# 400_FLAHS_MEMORY.net
KiCad netlist of a schematic drawn in Altium Designer
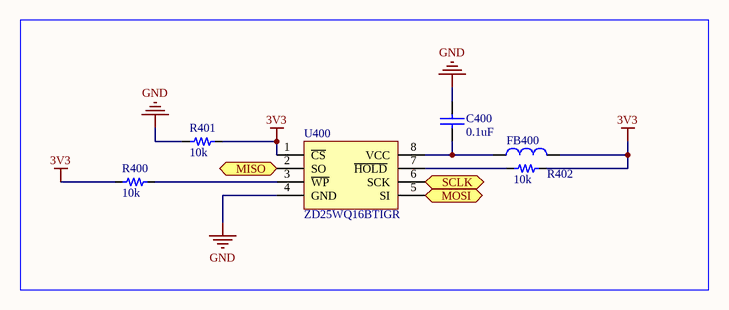
[diagram p0: 400_FLAHS_MEMORY.SchDoc]

(export (version "E")
  (design (tool "Eeschema 10.0.6"))
  (components
    (comp (ref "C400")
      (value "0.1uF")
      (footprint "0603_cap")
      (description "50V 100nF Y5V -20%~+80% 0603 Multilayer Ceramic Capacitors MLCC - SMD/SMT ROHS")
      (fields
        (field (name "MANUFACTURER") "Walsin Tech Corp")
        (field (name "MANUFACTURER PART NUMBER") "0603F104Z500CT")
      )
      (libsource (lib "shared_lib") (part "Cap_0.1uF_0603_50V"))
    )
    (comp (ref "FB400")
      (value "60OHM 2A")
      (footprint "0603_fb")
      (description "2A 1 100mΩ 60Ω@100MHz ±25% 0603 Ferrite Beads ROHS")
      (fields
        (field (name "MANUFACTURER") "TAI-TECH")
        (field (name "MANUFACTURER PART NUMBER") "HCB1608KF-600T20")
      )
      (libsource (lib "shared_lib") (part "FB_60_0603_2A"))
    )
    (comp (ref "R400")
      (value "10k")
      (footprint "0603_res")
      (description "RES SMD 10k OHM 5% 1/10W 0603")
      (fields (field (name "MANUFACTURER") "FOJAN") (field (name "MANUFACTURER PART NUMBER") "FRC0603J103TS"))
      (libsource (lib "shared_lib") (part "Res_10k_0603_1/10W"))
    )
    (comp (ref "R401")
      (value "10k")
      (footprint "0603_res")
      (description "RES SMD 10k OHM 5% 1/10W 0603")
      (fields (field (name "MANUFACTURER") "FOJAN") (field (name "MANUFACTURER PART NUMBER") "FRC0603J103TS"))
      (libsource (lib "shared_lib") (part "Res_10k_0603_1/10W"))
    )
    (comp (ref "R402")
      (value "10k")
      (footprint "0603_res")
      (description "RES SMD 10k OHM 5% 1/10W 0603")
      (fields (field (name "MANUFACTURER") "FOJAN") (field (name "MANUFACTURER PART NUMBER") "FRC0603J103TS"))
      (libsource (lib "shared_lib") (part "Res_10k_0603_1/10W"))
    )
    (comp (ref "U400")
      (value "ZD25WQ16BTIGR")
      (footprint "SOIC_8_3.9mm")
      (description "IC FLASH 16M SPI 85MHZ 8SOP")
      (fields (field (name "MANUFACTURER") "Zetta"))
      (libsource (lib "shared_lib") (part "IC_FLASH_ZD25WQ16BTIGR_8SOP"))
    )
  )
  (nets
    (net (code "1") (name "/MISO") (class "Default")
      (node (ref "U400") (pin "2") (pinfunction "SO_2") (pintype "passive"))
    )
    (net (code "2") (name "/MOSI") (class "Default")
      (node (ref "U400") (pin "5") (pinfunction "SI_5") (pintype "passive"))
    )
    (net (code "3") (name "/SCLK") (class "Default")
      (node (ref "U400") (pin "6") (pinfunction "SCK_6") (pintype "passive"))
    )
    (net (code "4") (name "3V3") (class "Default")
      (node (ref "FB400") (pin "2") (pinfunction "2_2") (pintype "passive"))
      (node (ref "R400") (pin "1") (pinfunction "1_1") (pintype "passive"))
      (node (ref "R401") (pin "2") (pinfunction "2_2") (pintype "passive"))
      (node (ref "R402") (pin "2") (pinfunction "2_2") (pintype "passive"))
      (node (ref "U400") (pin "1") (pinfunction "~{CS}_1") (pintype "passive"))
    )
    (net (code "5") (name "GND") (class "Default")
      (node (ref "C400") (pin "2") (pinfunction "2_2") (pintype "passive"))
      (node (ref "R401") (pin "1") (pinfunction "1_1") (pintype "passive"))
      (node (ref "U400") (pin "4") (pinfunction "GND_4") (pintype "passive"))
    )
    (net (code "6") (name "Net-(U400-VCC)") (class "Default")
      (node (ref "C400") (pin "1") (pinfunction "1_1") (pintype "passive"))
      (node (ref "FB400") (pin "1") (pinfunction "1_1") (pintype "passive"))
      (node (ref "U400") (pin "8") (pinfunction "VCC_8") (pintype "passive"))
    )
    (net (code "7") (name "Net-(U400-~{HOLD})") (class "Default")
      (node (ref "R402") (pin "1") (pinfunction "1_1") (pintype "passive"))
      (node (ref "U400") (pin "7") (pinfunction "~{HOLD}_7") (pintype "passive"))
    )
    (net (code "8") (name "Net-(U400-~{WP})") (class "Default")
      (node (ref "R400") (pin "2") (pinfunction "2_2") (pintype "passive"))
      (node (ref "U400") (pin "3") (pinfunction "~{WP}_3") (pintype "passive"))
    )
  )
)
